# Fablab_RFID_conroller_V1.net
KiCad netlist of a schematic drawn in EAGLE
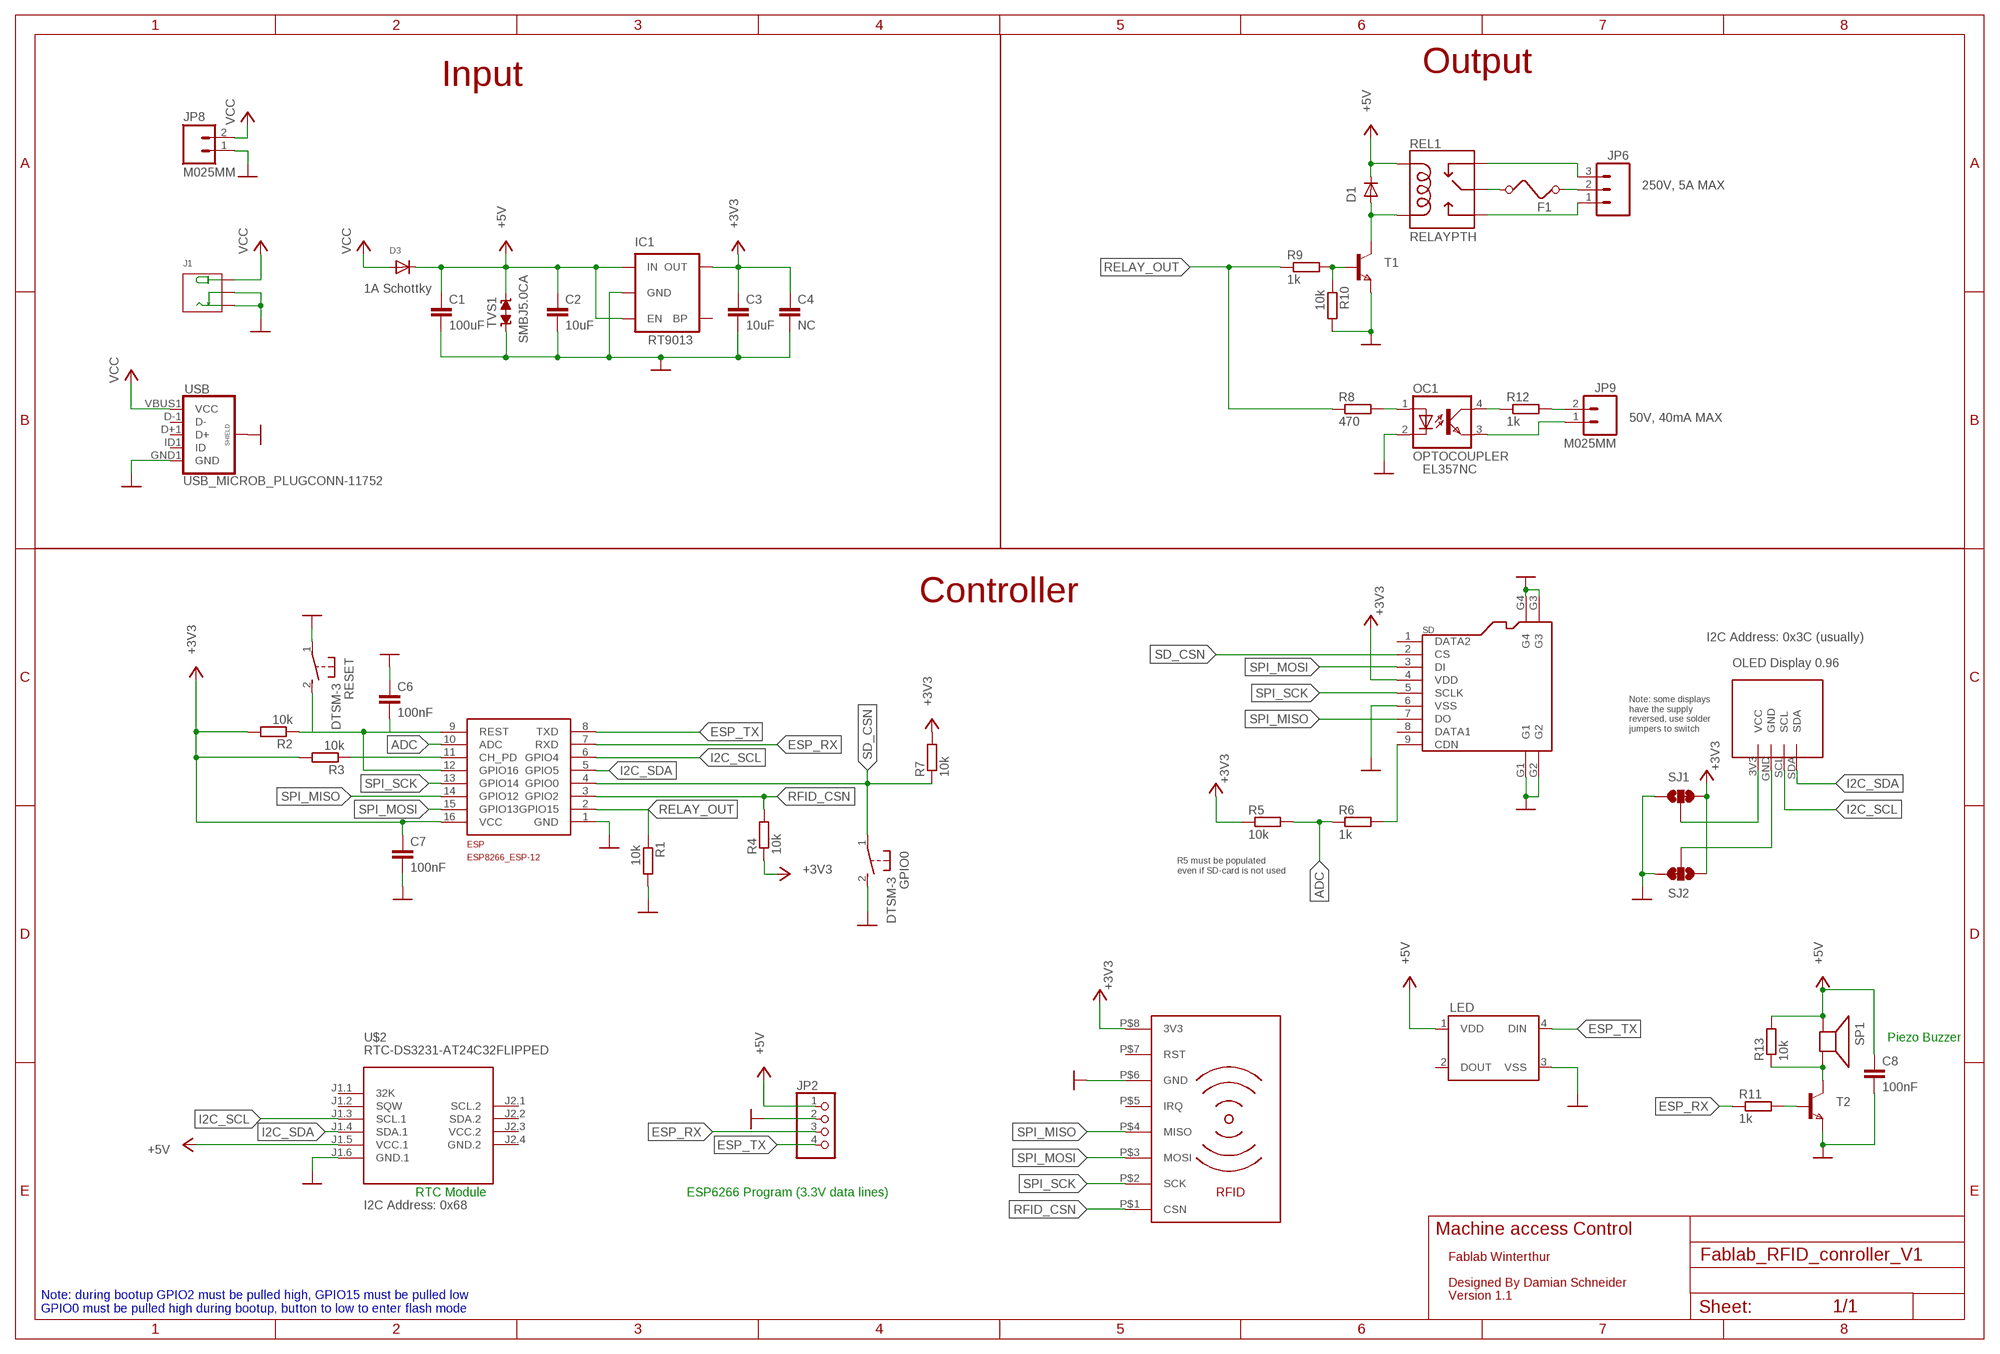
[diagram p0: schematic, sheet 1]

(export (version "E")
  (design (tool "Eeschema 10.0.6"))
  (components
    (comp (ref "C1")
      (value "100uF")
      (footprint "eagle-import:C1206")
      (libsource (lib "eagle-import") (part "C-EUC1206"))
    )
    (comp (ref "C2")
      (value "10uF")
      (footprint "eagle-import:C0805")
      (libsource (lib "eagle-import") (part "C-EUC0805"))
    )
    (comp (ref "C3")
      (value "10uF")
      (footprint "eagle-import:C0805")
      (libsource (lib "eagle-import") (part "C-EUC0805"))
    )
    (comp (ref "C4")
      (value "NC")
      (footprint "eagle-import:C1206")
      (libsource (lib "eagle-import") (part "C-EUC1206"))
    )
    (comp (ref "C6")
      (value "100nF")
      (footprint "eagle-import:C0603")
      (libsource (lib "eagle-import") (part "C-EUC0603"))
    )
    (comp (ref "C7")
      (value "100nF")
      (footprint "eagle-import:C0603")
      (libsource (lib "eagle-import") (part "C-EUC0603"))
    )
    (comp (ref "C8")
      (value "100nF")
      (footprint "eagle-import:C0603")
      (libsource (lib "eagle-import") (part "C-EUC0603"))
    )
    (comp (ref "D1")
      (value "DIODE-MINIMELF")
      (footprint "eagle-import:MINIMELF")
      (libsource (lib "eagle-import") (part "DIODE-MINIMELF"))
    )
    (comp (ref "D3")
      (value "DIODESMA")
      (footprint "eagle-import:SMADIODE")
      (libsource (lib "eagle-import") (part "DIODESMA"))
    )
    (comp (ref "ESP")
      (value "ESP8266_ESP-12")
      (footprint "eagle-import:ESP8266-ESP12")
      (libsource (lib "eagle-import") (part "ESP8266_ESP-12"))
    )
    (comp (ref "F1")
      (value "FUSE")
      (footprint "eagle-import:FUSE")
      (libsource (lib "eagle-import") (part "FUSE"))
    )
    (comp (ref "GPIO0")
      (value "DTSM-3")
      (footprint "eagle-import:DTSM-3")
      (libsource (lib "eagle-import") (part "DTSM-3"))
    )
    (comp (ref "IC1")
      (value "V_REG_LDOSMD")
      (footprint "eagle-import:SOT23-5")
      (libsource (lib "eagle-import") (part "V_REG_LDOSMD"))
    )
    (comp (ref "J1")
      (value "JACK-DC-3P-3410020P1")
      (footprint "eagle-import:PW-3P-2.1")
      (libsource (lib "eagle-import") (part "JACK-DC-3P-3410020P1"))
    )
    (comp (ref "JP2")
      (value "HEADER-1X476MIL")
      (footprint "eagle-import:1X04_ROUND_76")
      (libsource (lib "eagle-import") (part "HEADER-1X476MIL"))
    )
    (comp (ref "JP6")
      (value "M03-SCREW-5MM")
      (footprint "eagle-import:SCREWTERMINAL-5MM-3")
      (libsource (lib "eagle-import") (part "M03-SCREW-5MM"))
    )
    (comp (ref "JP8")
      (value "M025MM")
      (footprint "eagle-import:SCREWTERMINAL-5MM-2")
      (libsource (lib "eagle-import") (part "M025MM"))
    )
    (comp (ref "JP9")
      (value "M025MM")
      (footprint "eagle-import:SCREWTERMINAL-5MM-2")
      (libsource (lib "eagle-import") (part "M025MM"))
    )
    (comp (ref "LED")
      (value "WS2812B")
      (footprint "eagle-import:WS2812B")
      (libsource (lib "eagle-import") (part "WS2812B"))
    )
    (comp (ref "OC1")
      (value "OPTOCOUPLER")
      (footprint "eagle-import:SOP04")
      (libsource (lib "eagle-import") (part "OPTOCOUPLER"))
    )
    (comp (ref "OLED")
      (value "OLED_0.96_I2CNOHOLES")
      (footprint "eagle-import:OLED_0.96_I2C_NOHOLES")
      (libsource (lib "eagle-import") (part "OLED_0.96_I2CNOHOLES"))
    )
    (comp (ref "R1")
      (value "10k")
      (footprint "eagle-import:R0603")
      (libsource (lib "eagle-import") (part "R-EU_R0603"))
    )
    (comp (ref "R2")
      (value "10k")
      (footprint "eagle-import:R0603")
      (libsource (lib "eagle-import") (part "R-EU_R0603"))
    )
    (comp (ref "R3")
      (value "10k")
      (footprint "eagle-import:R0603")
      (libsource (lib "eagle-import") (part "R-EU_R0603"))
    )
    (comp (ref "R4")
      (value "10k")
      (footprint "eagle-import:R0603")
      (libsource (lib "eagle-import") (part "R-EU_R0603"))
    )
    (comp (ref "R5")
      (value "10k")
      (footprint "eagle-import:R0603")
      (libsource (lib "eagle-import") (part "R-EU_R0603"))
    )
    (comp (ref "R6")
      (value "1k")
      (footprint "eagle-import:R0603")
      (libsource (lib "eagle-import") (part "R-EU_R0603"))
    )
    (comp (ref "R7")
      (value "10k")
      (footprint "eagle-import:R0603")
      (libsource (lib "eagle-import") (part "R-EU_R0603"))
    )
    (comp (ref "R8")
      (value "470")
      (footprint "eagle-import:R0603")
      (libsource (lib "eagle-import") (part "R-EU_R0603"))
    )
    (comp (ref "R9")
      (value "1k")
      (footprint "eagle-import:R0603")
      (libsource (lib "eagle-import") (part "R-EU_R0603"))
    )
    (comp (ref "R10")
      (value "10k")
      (footprint "eagle-import:R0603")
      (libsource (lib "eagle-import") (part "R-EU_R0603"))
    )
    (comp (ref "R11")
      (value "1k")
      (footprint "eagle-import:R0603")
      (libsource (lib "eagle-import") (part "R-EU_R0603"))
    )
    (comp (ref "R12")
      (value "1k")
      (footprint "eagle-import:R0805")
      (libsource (lib "eagle-import") (part "R-EU_R0805"))
    )
    (comp (ref "R13")
      (value "10k")
      (footprint "eagle-import:R0603")
      (libsource (lib "eagle-import") (part "R-EU_R0603"))
    )
    (comp (ref "REL1")
      (value "RELAYPTH")
      (footprint "eagle-import:SRD-05VDC-SL-C")
      (libsource (lib "eagle-import") (part "RELAYPTH"))
    )
    (comp (ref "RESET")
      (value "DTSM-3")
      (footprint "eagle-import:DTSM-3")
      (libsource (lib "eagle-import") (part "DTSM-3"))
    )
    (comp (ref "RFID")
      (value "RFID_MODULE_RC522")
      (footprint "eagle-import:RFID-RC522-MODULE")
      (libsource (lib "eagle-import") (part "RFID_MODULE_RC522"))
    )
    (comp (ref "SD")
      (value "MICRO-SDCARD-CONNECTOR-3300060P1")
      (footprint "eagle-import:9P-SMD-W-RING")
      (libsource (lib "eagle-import") (part "MICRO-SDCARD-CONNECTOR-3300060P1"))
    )
    (comp (ref "SJ1")
      (value "JUMPER-PAD-3-2OF3_NC_BY_TRACE_LARGE")
      (footprint "eagle-import:PAD-JUMPER-3-2OF3_NC_BY_TRACE_YES_SILK_LARGE")
      (libsource (lib "eagle-import") (part "JUMPER-PAD-3-2OF3_NC_BY_TRACE_LARGE"))
    )
    (comp (ref "SJ2")
      (value "JUMPER-PAD-3-2OF3_NC_BY_TRACE_LARGE")
      (footprint "eagle-import:PAD-JUMPER-3-2OF3_NC_BY_TRACE_YES_SILK_LARGE")
      (libsource (lib "eagle-import") (part "JUMPER-PAD-3-2OF3_NC_BY_TRACE_LARGE"))
    )
    (comp (ref "SP1")
      (value "SPEAKER/AL60P")
      (footprint "eagle-import:AL60P")
      (libsource (lib "eagle-import") (part "SPEAKER/AL60P"))
    )
    (comp (ref "T1")
      (value "NPNSOT23")
      (footprint "eagle-import:SOT-23")
      (fields (field (name "MPN") "DSS20201L-7"))
      (libsource (lib "eagle-import") (part "NPNSOT23"))
    )
    (comp (ref "T2")
      (value "NPNSOT23")
      (footprint "eagle-import:SOT-23")
      (fields (field (name "MPN") "DSS20201L-7"))
      (libsource (lib "eagle-import") (part "NPNSOT23"))
    )
    (comp (ref "TVS1")
      (value "TVS-SMBJ")
      (footprint "eagle-import:SMBJ")
      (libsource (lib "eagle-import") (part "TVS-SMBJ"))
    )
    (comp (ref "U$2")
      (value "RTC-DS3231-AT24C32FLIPPED")
      (footprint "eagle-import:RTC-DS3231_FLIPPED")
      (libsource (lib "eagle-import") (part "RTC-DS3231-AT24C32FLIPPED"))
    )
    (comp (ref "USB")
      (value "USB_MICROB_PLUGCONN-11752")
      (footprint "eagle-import:USB-B-MICRO-SMD_V03")
      (libsource (lib "eagle-import") (part "USB_MICROB_PLUGCONN-11752"))
    )
  )
  (nets
    (net (code "1") (name "+3V3") (class "Default")
      (node (ref "C3") (pin "1") (pinfunction "1_1") (pintype "passive"))
      (node (ref "C4") (pin "1") (pinfunction "1_1") (pintype "passive"))
      (node (ref "C7") (pin "1") (pinfunction "1_1") (pintype "passive"))
      (node (ref "ESP") (pin "16") (pinfunction "VCC_16") (pintype "bidirectional"))
      (node (ref "IC1") (pin "5") (pinfunction "OUT_5") (pintype "passive"))
      (node (ref "R2") (pin "2") (pinfunction "2_2") (pintype "passive"))
      (node (ref "R3") (pin "2") (pinfunction "2_2") (pintype "passive"))
      (node (ref "R4") (pin "1") (pinfunction "1_1") (pintype "passive"))
      (node (ref "R5") (pin "1") (pinfunction "1_1") (pintype "passive"))
      (node (ref "R7") (pin "2") (pinfunction "2_2") (pintype "passive"))
      (node (ref "RFID") (pin "P$8") (pinfunction "3V3_P$8") (pintype "bidirectional"))
      (node (ref "SD") (pin "4") (pinfunction "VDD_4") (pintype "bidirectional"))
      (node (ref "SJ1") (pin "3") (pinfunction "3_3") (pintype "passive"))
      (node (ref "SJ2") (pin "1") (pinfunction "1_1") (pintype "passive"))
    )
    (net (code "2") (name "+5V") (class "Default")
      (node (ref "C1") (pin "1") (pinfunction "1_1") (pintype "passive"))
      (node (ref "C2") (pin "1") (pinfunction "1_1") (pintype "passive"))
      (node (ref "C8") (pin "1") (pinfunction "1_1") (pintype "passive"))
      (node (ref "D1") (pin "C") (pinfunction "C_C") (pintype "passive"))
      (node (ref "D3") (pin "C") (pinfunction "C_C") (pintype "passive"))
      (node (ref "IC1") (pin "1") (pinfunction "IN_1") (pintype "input"))
      (node (ref "IC1") (pin "3") (pinfunction "EN_3") (pintype "input"))
      (node (ref "JP2") (pin "1") (pinfunction "1_1") (pintype "passive"))
      (node (ref "LED") (pin "1") (pinfunction "VDD_1") (pintype "power_in"))
      (node (ref "R13") (pin "2") (pinfunction "2_2") (pintype "passive"))
      (node (ref "REL1") (pin "COIL1") (pinfunction "COIL1_COIL1") (pintype "bidirectional"))
      (node (ref "SP1") (pin "1") (pinfunction "+_1") (pintype "passive"))
      (node (ref "TVS1") (pin "C") (pinfunction "2_C") (pintype "passive"))
      (node (ref "U$2") (pin "J1.5") (pinfunction "VCC.1_J1.5") (pintype "power_in"))
    )
    (net (code "3") (name "/GND.2") (class "Default")
      (node (ref "U$2") (pin "J2.4") (pinfunction "GND.2_J2.4") (pintype "power_in"))
    )
    (net (code "4") (name "/VCC.2") (class "Default")
      (node (ref "U$2") (pin "J2.3") (pinfunction "VCC.2_J2.3") (pintype "power_in"))
    )
    (net (code "5") (name "ADC") (class "Default")
      (node (ref "ESP") (pin "10") (pinfunction "ADC_10") (pintype "bidirectional"))
      (node (ref "R5") (pin "2") (pinfunction "2_2") (pintype "passive"))
      (node (ref "R6") (pin "1") (pinfunction "1_1") (pintype "passive"))
    )
    (net (code "6") (name "ESP_RX") (class "Default")
      (node (ref "ESP") (pin "7") (pinfunction "RXD_7") (pintype "bidirectional"))
      (node (ref "JP2") (pin "3") (pinfunction "3_3") (pintype "passive"))
      (node (ref "R11") (pin "1") (pinfunction "1_1") (pintype "passive"))
    )
    (net (code "7") (name "ESP_TX") (class "Default")
      (node (ref "ESP") (pin "8") (pinfunction "TXD_8") (pintype "bidirectional"))
      (node (ref "JP2") (pin "4") (pinfunction "4_4") (pintype "passive"))
      (node (ref "LED") (pin "4") (pinfunction "DIN_4") (pintype "input"))
    )
    (net (code "8") (name "GND") (class "Default")
      (node (ref "C1") (pin "2") (pinfunction "2_2") (pintype "passive"))
      (node (ref "C2") (pin "2") (pinfunction "2_2") (pintype "passive"))
      (node (ref "C3") (pin "2") (pinfunction "2_2") (pintype "passive"))
      (node (ref "C4") (pin "2") (pinfunction "2_2") (pintype "passive"))
      (node (ref "C6") (pin "1") (pinfunction "1_1") (pintype "passive"))
      (node (ref "C7") (pin "2") (pinfunction "2_2") (pintype "passive"))
      (node (ref "C8") (pin "2") (pinfunction "2_2") (pintype "passive"))
      (node (ref "ESP") (pin "1") (pinfunction "GND_1") (pintype "bidirectional"))
      (node (ref "GPIO0") (pin "2") (pinfunction "2_2") (pintype "passive"))
      (node (ref "IC1") (pin "2") (pinfunction "GND_2") (pintype "input"))
      (node (ref "J1") (pin "-1") (pinfunction "-_-1") (pintype "bidirectional"))
      (node (ref "J1") (pin "-2") (pinfunction "CDN_-2") (pintype "bidirectional"))
      (node (ref "JP2") (pin "2") (pinfunction "2_2") (pintype "passive"))
      (node (ref "JP8") (pin "1") (pinfunction "1_1") (pintype "passive"))
      (node (ref "LED") (pin "3") (pinfunction "VSS_3") (pintype "power_in"))
      (node (ref "OC1") (pin "2") (pinfunction "C_2") (pintype "passive"))
      (node (ref "R1") (pin "2") (pinfunction "2_2") (pintype "passive"))
      (node (ref "R10") (pin "2") (pinfunction "2_2") (pintype "passive"))
      (node (ref "RESET") (pin "1") (pinfunction "1_1") (pintype "passive"))
      (node (ref "RFID") (pin "P$6") (pinfunction "GND_P$6") (pintype "bidirectional"))
      (node (ref "SD") (pin "6") (pinfunction "VSS_6") (pintype "bidirectional"))
      (node (ref "SD") (pin "G1") (pinfunction "G1_G1") (pintype "bidirectional"))
      (node (ref "SD") (pin "G2") (pinfunction "G2_G2") (pintype "bidirectional"))
      (node (ref "SD") (pin "G3") (pinfunction "G3_G3") (pintype "bidirectional"))
      (node (ref "SD") (pin "G4") (pinfunction "G4_G4") (pintype "bidirectional"))
      (node (ref "SJ1") (pin "1") (pinfunction "1_1") (pintype "passive"))
      (node (ref "SJ2") (pin "3") (pinfunction "3_3") (pintype "passive"))
      (node (ref "T1") (pin "2") (pinfunction "E_2") (pintype "passive"))
      (node (ref "T2") (pin "2") (pinfunction "E_2") (pintype "passive"))
      (node (ref "TVS1") (pin "A") (pinfunction "1_A") (pintype "passive"))
      (node (ref "U$2") (pin "J1.6") (pinfunction "GND.1_J1.6") (pintype "power_in"))
      (node (ref "USB") (pin "GND1") (pinfunction "GND_GND1") (pintype "bidirectional"))
      (node (ref "USB") (pin "SHIELD1") (pinfunction "SHIELD_SHIELD1") (pintype "bidirectional"))
      (node (ref "USB") (pin "SHIELD2") (pinfunction "SHIELD_SHIELD2") (pintype "bidirectional"))
      (node (ref "USB") (pin "SHIELD3") (pinfunction "SHIELD_SHIELD3") (pintype "bidirectional"))
    )
    (net (code "9") (name "I2C_SCL") (class "Default")
      (node (ref "ESP") (pin "6") (pinfunction "GPIO4_6") (pintype "bidirectional"))
      (node (ref "OLED") (pin "SCL") (pinfunction "SCL_SCL") (pintype "bidirectional"))
      (node (ref "U$2") (pin "J1.3") (pinfunction "SCL.1_J1.3") (pintype "bidirectional"))
    )
    (net (code "10") (name "I2C_SDA") (class "Default")
      (node (ref "ESP") (pin "5") (pinfunction "GPIO5_5") (pintype "bidirectional"))
      (node (ref "OLED") (pin "SDA") (pinfunction "SDA_SDA") (pintype "bidirectional"))
      (node (ref "U$2") (pin "J1.4") (pinfunction "SDA.1_J1.4") (pintype "bidirectional"))
    )
    (net (code "11") (name "Net-(ESP-CH_PD)") (class "Default")
      (node (ref "ESP") (pin "11") (pinfunction "CH_PD_11") (pintype "bidirectional"))
      (node (ref "R3") (pin "1") (pinfunction "1_1") (pintype "passive"))
    )
    (net (code "12") (name "Net-(ESP-GPIO16)") (class "Default")
      (node (ref "C6") (pin "2") (pinfunction "2_2") (pintype "passive"))
      (node (ref "ESP") (pin "12") (pinfunction "GPIO16_12") (pintype "bidirectional"))
      (node (ref "ESP") (pin "9") (pinfunction "REST_9") (pintype "bidirectional"))
      (node (ref "R2") (pin "1") (pinfunction "1_1") (pintype "passive"))
      (node (ref "RESET") (pin "2") (pinfunction "2_2") (pintype "passive"))
    )
    (net (code "13") (name "Net-(F1-Pad1)") (class "Default")
      (node (ref "F1") (pin "1") (pinfunction "1_1") (pintype "passive"))
      (node (ref "JP6") (pin "2") (pinfunction "2_2") (pintype "passive"))
    )
    (net (code "14") (name "Net-(F1-Pad2)") (class "Default")
      (node (ref "F1") (pin "2") (pinfunction "2_2") (pintype "passive"))
      (node (ref "REL1") (pin "SWCOMMON") (pinfunction "SWCOMMON_SWCOMMON") (pintype "bidirectional"))
    )
    (net (code "15") (name "Net-(JP9-Pad2)") (class "Default")
      (node (ref "JP9") (pin "2") (pinfunction "2_2") (pintype "passive"))
      (node (ref "R12") (pin "2") (pinfunction "2_2") (pintype "passive"))
    )
    (net (code "16") (name "Net-(OC1-A)") (class "Default")
      (node (ref "OC1") (pin "1") (pinfunction "A_1") (pintype "passive"))
      (node (ref "R8") (pin "2") (pinfunction "2_2") (pintype "passive"))
    )
    (net (code "17") (name "Net-(OC1-COL)") (class "Default")
      (node (ref "OC1") (pin "4") (pinfunction "COL_4") (pintype "passive"))
      (node (ref "R12") (pin "1") (pinfunction "1_1") (pintype "passive"))
    )
    (net (code "18") (name "Net-(OC1-EMIT)") (class "Default")
      (node (ref "JP9") (pin "1") (pinfunction "1_1") (pintype "passive"))
      (node (ref "OC1") (pin "3") (pinfunction "EMIT_3") (pintype "passive"))
    )
    (net (code "19") (name "Net-(OLED-PadGND)") (class "Default")
      (node (ref "OLED") (pin "GND") (pinfunction "GND_GND") (pintype "bidirectional"))
      (node (ref "SJ2") (pin "2") (pinfunction "2_2") (pintype "passive"))
    )
    (net (code "20") (name "Net-(OLED-VCC)") (class "Default")
      (node (ref "OLED") (pin "3V3") (pinfunction "VCC_3V3") (pintype "bidirectional"))
      (node (ref "SJ1") (pin "2") (pinfunction "2_2") (pintype "passive"))
    )
    (net (code "21") (name "Net-(REL1-SWCLOSE)") (class "Default")
      (node (ref "JP6") (pin "3") (pinfunction "3_3") (pintype "passive"))
      (node (ref "REL1") (pin "SW_NC") (pinfunction "SWCLOSE_SW_NC") (pintype "bidirectional"))
    )
    (net (code "22") (name "Net-(REL1-SWOPEN)") (class "Default")
      (node (ref "JP6") (pin "1") (pinfunction "1_1") (pintype "passive"))
      (node (ref "REL1") (pin "SW_NO") (pinfunction "SWOPEN_SW_NO") (pintype "bidirectional"))
    )
    (net (code "23") (name "Net-(SD-CDN)") (class "Default")
      (node (ref "R6") (pin "2") (pinfunction "2_2") (pintype "passive"))
      (node (ref "SD") (pin "9") (pinfunction "CDN_9") (pintype "bidirectional"))
    )
    (net (code "24") (name "Net-(SP1--)") (class "Default")
      (node (ref "R13") (pin "1") (pinfunction "1_1") (pintype "passive"))
      (node (ref "SP1") (pin "2") (pinfunction "-_2") (pintype "passive"))
      (node (ref "T2") (pin "1") (pinfunction "C_1") (pintype "passive"))
    )
    (net (code "25") (name "Net-(T1-B)") (class "Default")
      (node (ref "R10") (pin "1") (pinfunction "1_1") (pintype "passive"))
      (node (ref "R9") (pin "2") (pinfunction "2_2") (pintype "passive"))
      (node (ref "T1") (pin "3") (pinfunction "B_3") (pintype "passive"))
    )
    (net (code "26") (name "Net-(T1-C)") (class "Default")
      (node (ref "D1") (pin "A") (pinfunction "A_A") (pintype "passive"))
      (node (ref "REL1") (pin "COIL0") (pinfunction "COIL0_COIL0") (pintype "bidirectional"))
      (node (ref "T1") (pin "1") (pinfunction "C_1") (pintype "passive"))
    )
    (net (code "27") (name "Net-(T2-B)") (class "Default")
      (node (ref "R11") (pin "2") (pinfunction "2_2") (pintype "passive"))
      (node (ref "T2") (pin "3") (pinfunction "B_3") (pintype "passive"))
    )
    (net (code "28") (name "RELAY_OUT") (class "Default")
      (node (ref "ESP") (pin "2") (pinfunction "GPIO15_2") (pintype "bidirectional"))
      (node (ref "R1") (pin "1") (pinfunction "1_1") (pintype "passive"))
      (node (ref "R8") (pin "1") (pinfunction "1_1") (pintype "passive"))
      (node (ref "R9") (pin "1") (pinfunction "1_1") (pintype "passive"))
    )
    (net (code "29") (name "RFID_CSN") (class "Default")
      (node (ref "ESP") (pin "3") (pinfunction "GPIO2_3") (pintype "bidirectional"))
      (node (ref "R4") (pin "2") (pinfunction "2_2") (pintype "passive"))
      (node (ref "RFID") (pin "P$1") (pinfunction "CSN_P$1") (pintype "bidirectional"))
    )
    (net (code "30") (name "SD_CSN") (class "Default")
      (node (ref "ESP") (pin "4") (pinfunction "GPIO0_4") (pintype "bidirectional"))
      (node (ref "GPIO0") (pin "1") (pinfunction "1_1") (pintype "passive"))
      (node (ref "R7") (pin "1") (pinfunction "1_1") (pintype "passive"))
      (node (ref "SD") (pin "2") (pinfunction "CS_2") (pintype "bidirectional"))
    )
    (net (code "31") (name "SPI_MISO") (class "Default")
      (node (ref "ESP") (pin "14") (pinfunction "GPIO12_14") (pintype "bidirectional"))
      (node (ref "RFID") (pin "P$4") (pinfunction "MISO_P$4") (pintype "bidirectional"))
      (node (ref "SD") (pin "7") (pinfunction "DO_7") (pintype "bidirectional"))
    )
    (net (code "32") (name "SPI_MOSI") (class "Default")
      (node (ref "ESP") (pin "15") (pinfunction "GPIO13_15") (pintype "bidirectional"))
      (node (ref "RFID") (pin "P$3") (pinfunction "MOSI_P$3") (pintype "bidirectional"))
      (node (ref "SD") (pin "3") (pinfunction "DI_3") (pintype "bidirectional"))
    )
    (net (code "33") (name "SPI_SCK") (class "Default")
      (node (ref "ESP") (pin "13") (pinfunction "GPIO14_13") (pintype "bidirectional"))
      (node (ref "RFID") (pin "P$2") (pinfunction "SCK_P$2") (pintype "bidirectional"))
      (node (ref "SD") (pin "5") (pinfunction "SCLK_5") (pintype "bidirectional"))
    )
    (net (code "34") (name "VCC") (class "Default")
      (node (ref "D3") (pin "A") (pinfunction "A_A") (pintype "passive"))
      (node (ref "J1") (pin "+") (pinfunction "+_+") (pintype "bidirectional"))
      (node (ref "JP8") (pin "2") (pinfunction "2_2") (pintype "passive"))
      (node (ref "USB") (pin "VBUS1") (pinfunction "VCC_VBUS1") (pintype "bidirectional"))
    )
    (net (code "35") (name "unconnected-(IC1-BP-Pad4)") (class "Default")
      (node (ref "IC1") (pin "4") (pinfunction "BP_4") (pintype "input"))
    )
    (net (code "36") (name "unconnected-(LED-DOUT-Pad2)") (class "Default")
      (node (ref "LED") (pin "2") (pinfunction "DOUT_2") (pintype "output"))
    )
    (net (code "37") (name "unconnected-(RFID-IRQ-PadP$5)") (class "Default")
      (node (ref "RFID") (pin "P$5") (pinfunction "IRQ_P$5") (pintype "bidirectional"))
    )
    (net (code "38") (name "unconnected-(RFID-RST-PadP$7)") (class "Default")
      (node (ref "RFID") (pin "P$7") (pinfunction "RST_P$7") (pintype "bidirectional"))
    )
    (net (code "39") (name "unconnected-(SD-DATA1-Pad8)") (class "Default")
      (node (ref "SD") (pin "8") (pinfunction "DATA1_8") (pintype "bidirectional"))
    )
    (net (code "40") (name "unconnected-(SD-DATA2-Pad1)") (class "Default")
      (node (ref "SD") (pin "1") (pinfunction "DATA2_1") (pintype "bidirectional"))
    )
    (net (code "41") (name "unconnected-(U$2-32K-PadJ1.1)") (class "Default")
      (node (ref "U$2") (pin "J1.1") (pinfunction "32K_J1.1") (pintype "bidirectional"))
    )
    (net (code "42") (name "unconnected-(U$2-SCL.2-PadJ2.1)") (class "Default")
      (node (ref "U$2") (pin "J2.1") (pinfunction "SCL.2_J2.1") (pintype "bidirectional"))
    )
    (net (code "43") (name "unconnected-(U$2-SDA.2-PadJ2.2)") (class "Default")
      (node (ref "U$2") (pin "J2.2") (pinfunction "SDA.2_J2.2") (pintype "bidirectional"))
    )
    (net (code "44") (name "unconnected-(U$2-SQW-PadJ1.2)") (class "Default")
      (node (ref "U$2") (pin "J1.2") (pinfunction "SQW_J1.2") (pintype "bidirectional"))
    )
    (net (code "45") (name "unconnected-(USB-D+-PadD+1)") (class "Default")
      (node (ref "USB") (pin "D+1") (pinfunction "D+_D+1") (pintype "bidirectional"))
    )
    (net (code "46") (name "unconnected-(USB-D--PadD-1)") (class "Default")
      (node (ref "USB") (pin "D-1") (pinfunction "D-_D-1") (pintype "bidirectional"))
    )
    (net (code "47") (name "unconnected-(USB-ID-PadID1)") (class "Default")
      (node (ref "USB") (pin "ID1") (pinfunction "ID_ID1") (pintype "bidirectional"))
    )
  )
)
